# Interconnect_board_v1p4.net
KiCad netlist of a schematic drawn in EAGLE
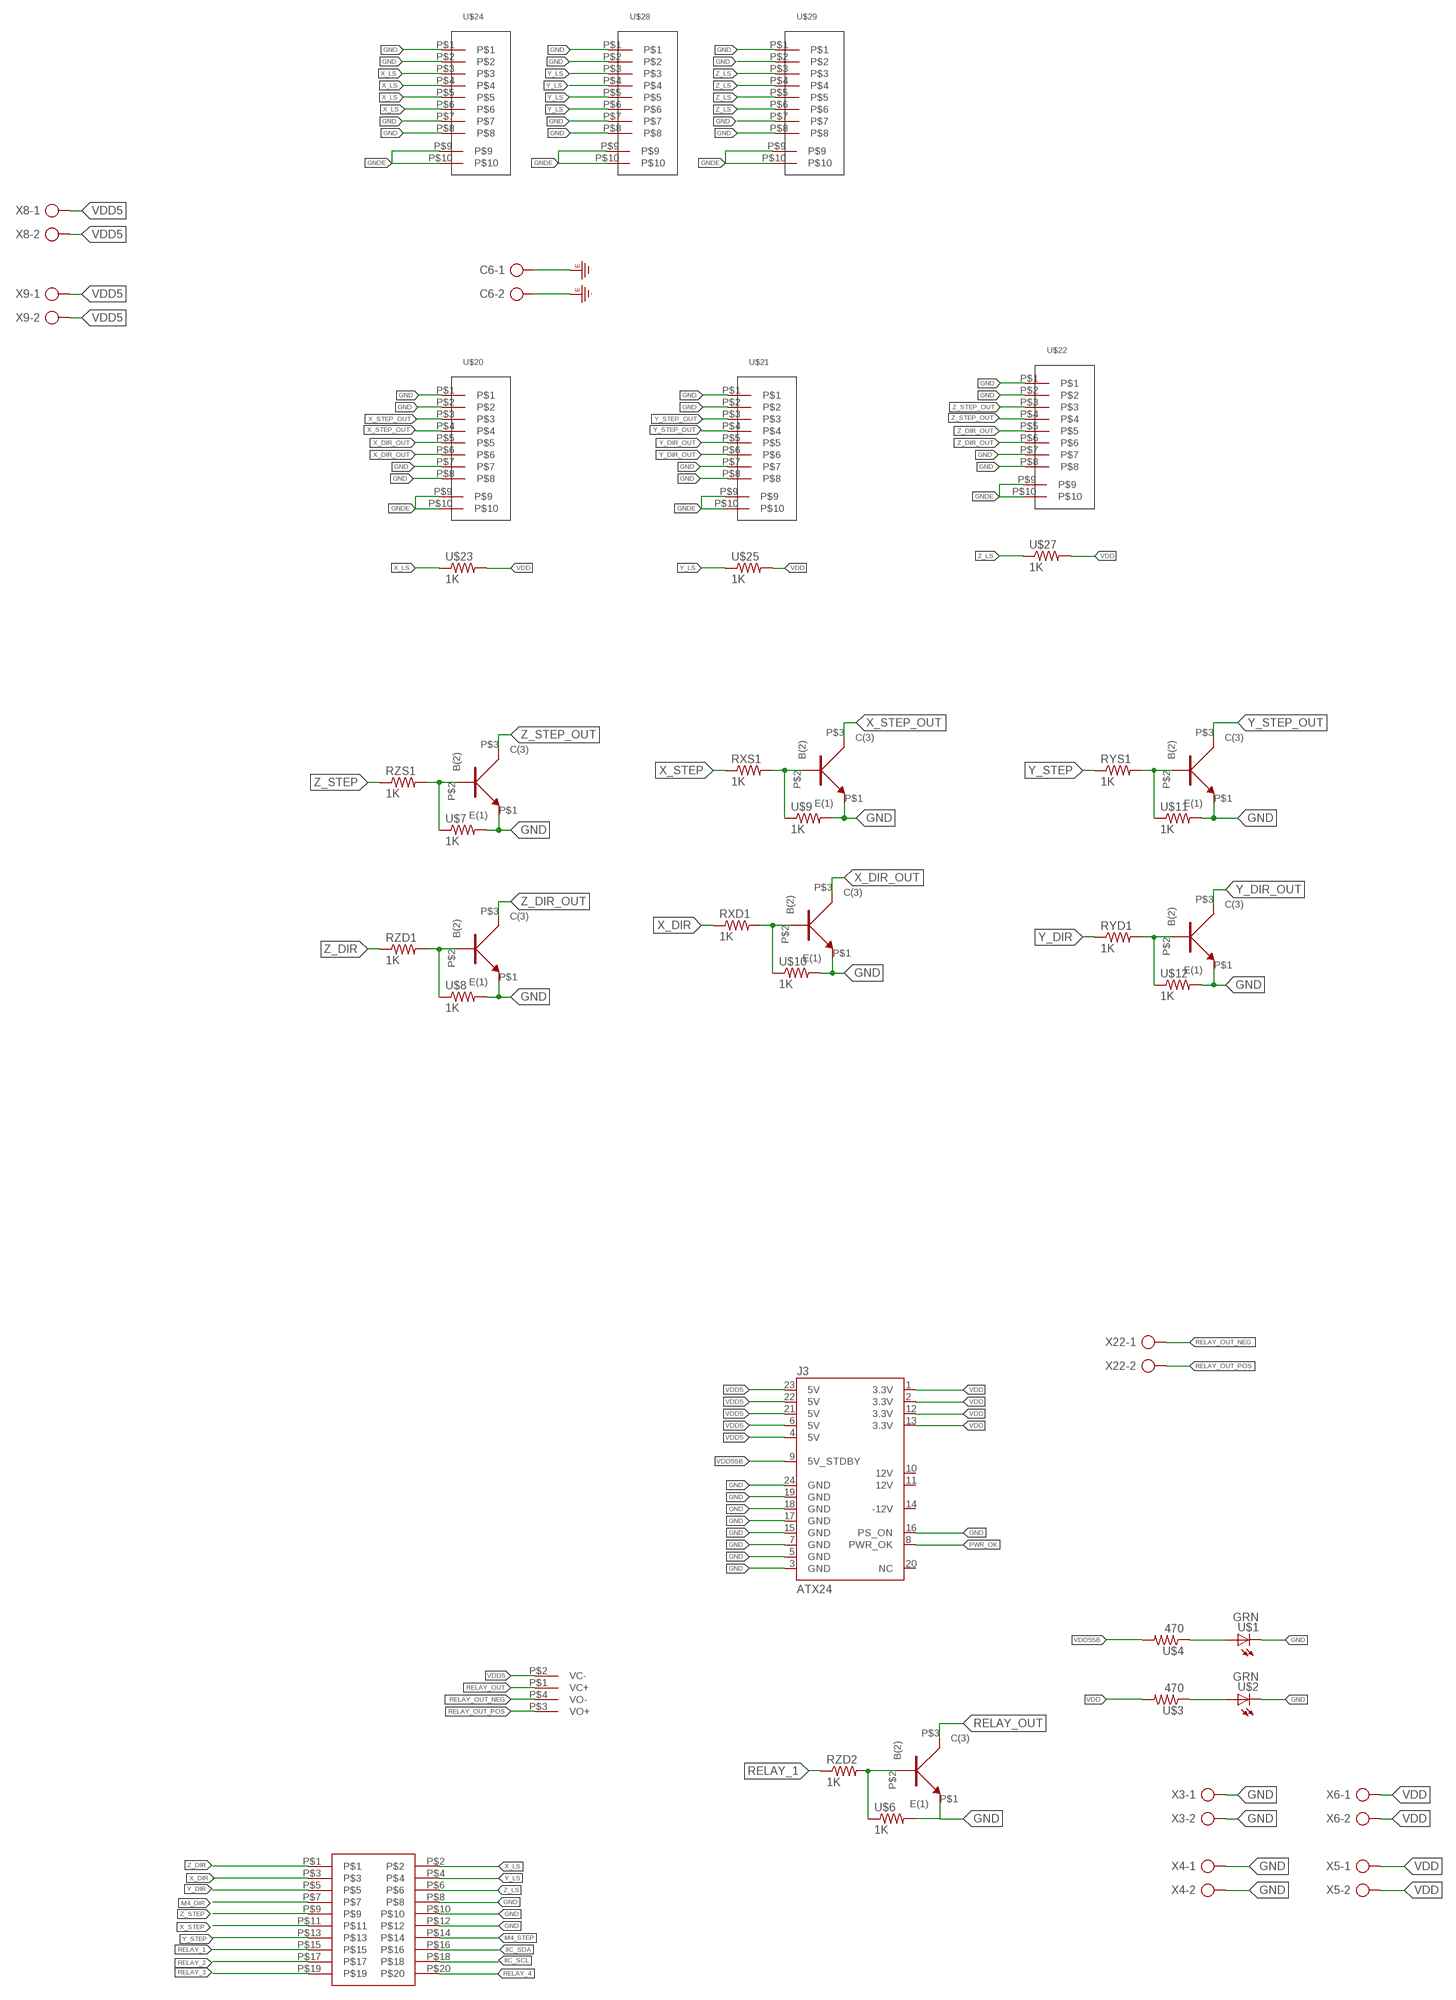
[diagram p0: schematic, sheet 1]

(export (version "E")
  (design (tool "Eeschema 10.0.6"))
  (components
    (comp (ref "C6")
      (value "AK300/2")
      (footprint "eagle-import:AK300_2")
      (libsource (lib "eagle-import") (part "AK300/2"))
    )
    (comp (ref "J3")
      (value "ATX24")
      (footprint "eagle-import:ATX24_STRAIGHT")
      (libsource (lib "eagle-import") (part "ATX24"))
    )
    (comp (ref "RXD1")
      (value "R_0805_1K")
      (footprint "eagle-import:R_0805_1K")
      (libsource (lib "eagle-import") (part "R_0805_1K"))
    )
    (comp (ref "RXS1")
      (value "R_0805_1K")
      (footprint "eagle-import:R_0805_1K")
      (libsource (lib "eagle-import") (part "R_0805_1K"))
    )
    (comp (ref "RYD1")
      (value "R_0805_1K")
      (footprint "eagle-import:R_0805_1K")
      (libsource (lib "eagle-import") (part "R_0805_1K"))
    )
    (comp (ref "RYS1")
      (value "R_0805_1K")
      (footprint "eagle-import:R_0805_1K")
      (libsource (lib "eagle-import") (part "R_0805_1K"))
    )
    (comp (ref "RZD1")
      (value "R_0805_1K")
      (footprint "eagle-import:R_0805_1K")
      (libsource (lib "eagle-import") (part "R_0805_1K"))
    )
    (comp (ref "RZD2")
      (value "R_0805_1K")
      (footprint "eagle-import:R_0805_1K")
      (libsource (lib "eagle-import") (part "R_0805_1K"))
    )
    (comp (ref "RZS1")
      (value "R_0805_1K")
      (footprint "eagle-import:R_0805_1K")
      (libsource (lib "eagle-import") (part "R_0805_1K"))
    )
    (comp (ref "U$1")
      (value "LED_0805_GREEN")
      (footprint "eagle-import:LED_0805_GREEN")
      (libsource (lib "eagle-import") (part "LED_0805_GREEN"))
    )
    (comp (ref "U$2")
      (value "LED_0805_GREEN")
      (footprint "eagle-import:LED_0805_GREEN")
      (libsource (lib "eagle-import") (part "LED_0805_GREEN"))
    )
    (comp (ref "U$3")
      (value "R_0805_470")
      (footprint "eagle-import:R_0805_470")
      (libsource (lib "eagle-import") (part "R_0805_470"))
    )
    (comp (ref "U$4")
      (value "R_0805_470")
      (footprint "eagle-import:R_0805_470")
      (libsource (lib "eagle-import") (part "R_0805_470"))
    )
    (comp (ref "U$5")
      (value "RELAY_KYOTO_KF0604D")
      (footprint "eagle-import:RELAY_KYOTO_KF0604D")
      (libsource (lib "eagle-import") (part "RELAY_KYOTO_KF0604D"))
    )
    (comp (ref "U$6")
      (value "R_0805_1K")
      (footprint "eagle-import:R_0805_1K")
      (libsource (lib "eagle-import") (part "R_0805_1K"))
    )
    (comp (ref "U$7")
      (value "R_0805_1K")
      (footprint "eagle-import:R_0805_1K")
      (libsource (lib "eagle-import") (part "R_0805_1K"))
    )
    (comp (ref "U$8")
      (value "R_0805_1K")
      (footprint "eagle-import:R_0805_1K")
      (libsource (lib "eagle-import") (part "R_0805_1K"))
    )
    (comp (ref "U$9")
      (value "R_0805_1K")
      (footprint "eagle-import:R_0805_1K")
      (libsource (lib "eagle-import") (part "R_0805_1K"))
    )
    (comp (ref "U$10")
      (value "R_0805_1K")
      (footprint "eagle-import:R_0805_1K")
      (libsource (lib "eagle-import") (part "R_0805_1K"))
    )
    (comp (ref "U$11")
      (value "R_0805_1K")
      (footprint "eagle-import:R_0805_1K")
      (libsource (lib "eagle-import") (part "R_0805_1K"))
    )
    (comp (ref "U$12")
      (value "R_0805_1K")
      (footprint "eagle-import:R_0805_1K")
      (libsource (lib "eagle-import") (part "R_0805_1K"))
    )
    (comp (ref "U$13")
      (value "TRANS_NPN")
      (footprint "eagle-import:TO_92_STRAIGHT")
      (libsource (lib "eagle-import") (part "TRANS_NPN"))
    )
    (comp (ref "U$14")
      (value "TRANS_NPN")
      (footprint "eagle-import:TO_92_STRAIGHT")
      (libsource (lib "eagle-import") (part "TRANS_NPN"))
    )
    (comp (ref "U$15")
      (value "TRANS_NPN")
      (footprint "eagle-import:TO_92_STRAIGHT")
      (libsource (lib "eagle-import") (part "TRANS_NPN"))
    )
    (comp (ref "U$16")
      (value "TRANS_NPN")
      (footprint "eagle-import:TO_92_STRAIGHT")
      (libsource (lib "eagle-import") (part "TRANS_NPN"))
    )
    (comp (ref "U$17")
      (value "TRANS_NPN")
      (footprint "eagle-import:TO_92_STRAIGHT")
      (libsource (lib "eagle-import") (part "TRANS_NPN"))
    )
    (comp (ref "U$18")
      (value "TRANS_NPN")
      (footprint "eagle-import:TO_92_STRAIGHT")
      (libsource (lib "eagle-import") (part "TRANS_NPN"))
    )
    (comp (ref "U$19")
      (value "TRANS_NPN")
      (footprint "eagle-import:TO_92_STRAIGHT")
      (libsource (lib "eagle-import") (part "TRANS_NPN"))
    )
    (comp (ref "U$20")
      (value "RJ45_SMTRJ")
      (footprint "eagle-import:RJ45_SMT")
      (libsource (lib "eagle-import") (part "RJ45_SMTRJ"))
    )
    (comp (ref "U$21")
      (value "RJ45_SMTRJ")
      (footprint "eagle-import:RJ45_SMT")
      (libsource (lib "eagle-import") (part "RJ45_SMTRJ"))
    )
    (comp (ref "U$22")
      (value "RJ45_SMTRJ")
      (footprint "eagle-import:RJ45_SMT")
      (libsource (lib "eagle-import") (part "RJ45_SMTRJ"))
    )
    (comp (ref "U$23")
      (value "R_0805_1K")
      (footprint "eagle-import:R_0805_1K")
      (libsource (lib "eagle-import") (part "R_0805_1K"))
    )
    (comp (ref "U$24")
      (value "RJ45_SMTRJ")
      (footprint "eagle-import:RJ45_SMT")
      (libsource (lib "eagle-import") (part "RJ45_SMTRJ"))
    )
    (comp (ref "U$25")
      (value "R_0805_1K")
      (footprint "eagle-import:R_0805_1K")
      (libsource (lib "eagle-import") (part "R_0805_1K"))
    )
    (comp (ref "U$26")
      (value "2_X_10_HEADER_GENERIC")
      (footprint "eagle-import:2_X_10_.1_INCH")
      (libsource (lib "eagle-import") (part "2_X_10_HEADER_GENERIC"))
    )
    (comp (ref "U$27")
      (value "R_0805_1K")
      (footprint "eagle-import:R_0805_1K")
      (libsource (lib "eagle-import") (part "R_0805_1K"))
    )
    (comp (ref "U$28")
      (value "RJ45_SMTRJ")
      (footprint "eagle-import:RJ45_SMT")
      (libsource (lib "eagle-import") (part "RJ45_SMTRJ"))
    )
    (comp (ref "U$29")
      (value "RJ45_SMTRJ")
      (footprint "eagle-import:RJ45_SMT")
      (libsource (lib "eagle-import") (part "RJ45_SMTRJ"))
    )
    (comp (ref "X3")
      (value "AK300/2")
      (footprint "eagle-import:AK300_2")
      (libsource (lib "eagle-import") (part "AK300/2"))
    )
    (comp (ref "X4")
      (value "AK300/2")
      (footprint "eagle-import:AK300_2")
      (libsource (lib "eagle-import") (part "AK300/2"))
    )
    (comp (ref "X5")
      (value "AK300/2")
      (footprint "eagle-import:AK300_2")
      (libsource (lib "eagle-import") (part "AK300/2"))
    )
    (comp (ref "X6")
      (value "AK300/2")
      (footprint "eagle-import:AK300_2")
      (libsource (lib "eagle-import") (part "AK300/2"))
    )
    (comp (ref "X8")
      (value "AK300/2")
      (footprint "eagle-import:AK300_2")
      (libsource (lib "eagle-import") (part "AK300/2"))
    )
    (comp (ref "X9")
      (value "AK300/2")
      (footprint "eagle-import:AK300_2")
      (libsource (lib "eagle-import") (part "AK300/2"))
    )
    (comp (ref "X22")
      (value "AK300/2")
      (footprint "eagle-import:AK300_2")
      (libsource (lib "eagle-import") (part "AK300/2"))
    )
  )
  (nets
    (net (code "1") (name "GND") (class "Default")
      (node (ref "J3") (pin "15") (pinfunction "GND_15") (pintype "bidirectional"))
      (node (ref "J3") (pin "16") (pinfunction "PS_ON_16") (pintype "bidirectional"))
      (node (ref "J3") (pin "17") (pinfunction "GND_17") (pintype "bidirectional"))
      (node (ref "J3") (pin "18") (pinfunction "GND_18") (pintype "bidirectional"))
      (node (ref "J3") (pin "19") (pinfunction "GND_19") (pintype "bidirectional"))
      (node (ref "J3") (pin "24") (pinfunction "GND_24") (pintype "bidirectional"))
      (node (ref "J3") (pin "3") (pinfunction "GND_3") (pintype "bidirectional"))
      (node (ref "J3") (pin "5") (pinfunction "GND_5") (pintype "bidirectional"))
      (node (ref "J3") (pin "7") (pinfunction "GND_7") (pintype "bidirectional"))
      (node (ref "U$1") (pin "C") (pinfunction "C_C") (pintype "passive"))
      (node (ref "U$10") (pin "2") (pinfunction "2_2") (pintype "passive"))
      (node (ref "U$11") (pin "2") (pinfunction "2_2") (pintype "passive"))
      (node (ref "U$12") (pin "2") (pinfunction "2_2") (pintype "passive"))
      (node (ref "U$13") (pin "P$1") (pinfunction "E(1)_P$1") (pintype "output"))
      (node (ref "U$14") (pin "P$1") (pinfunction "E(1)_P$1") (pintype "output"))
      (node (ref "U$15") (pin "P$1") (pinfunction "E(1)_P$1") (pintype "output"))
      (node (ref "U$16") (pin "P$1") (pinfunction "E(1)_P$1") (pintype "output"))
      (node (ref "U$17") (pin "P$1") (pinfunction "E(1)_P$1") (pintype "output"))
      (node (ref "U$18") (pin "P$1") (pinfunction "E(1)_P$1") (pintype "output"))
      (node (ref "U$19") (pin "P$1") (pinfunction "E(1)_P$1") (pintype "output"))
      (node (ref "U$2") (pin "C") (pinfunction "C_C") (pintype "passive"))
      (node (ref "U$20") (pin "P$1") (pinfunction "P$1_P$1") (pintype "bidirectional"))
      (node (ref "U$20") (pin "P$2") (pinfunction "P$2_P$2") (pintype "bidirectional"))
      (node (ref "U$20") (pin "P$7") (pinfunction "P$7_P$7") (pintype "bidirectional"))
      (node (ref "U$20") (pin "P$8") (pinfunction "P$8_P$8") (pintype "bidirectional"))
      (node (ref "U$21") (pin "P$1") (pinfunction "P$1_P$1") (pintype "bidirectional"))
      (node (ref "U$21") (pin "P$2") (pinfunction "P$2_P$2") (pintype "bidirectional"))
      (node (ref "U$21") (pin "P$7") (pinfunction "P$7_P$7") (pintype "bidirectional"))
      (node (ref "U$21") (pin "P$8") (pinfunction "P$8_P$8") (pintype "bidirectional"))
      (node (ref "U$22") (pin "P$1") (pinfunction "P$1_P$1") (pintype "bidirectional"))
      (node (ref "U$22") (pin "P$2") (pinfunction "P$2_P$2") (pintype "bidirectional"))
      (node (ref "U$22") (pin "P$7") (pinfunction "P$7_P$7") (pintype "bidirectional"))
      (node (ref "U$22") (pin "P$8") (pinfunction "P$8_P$8") (pintype "bidirectional"))
      (node (ref "U$24") (pin "P$1") (pinfunction "P$1_P$1") (pintype "bidirectional"))
      (node (ref "U$24") (pin "P$2") (pinfunction "P$2_P$2") (pintype "bidirectional"))
      (node (ref "U$24") (pin "P$7") (pinfunction "P$7_P$7") (pintype "bidirectional"))
      (node (ref "U$24") (pin "P$8") (pinfunction "P$8_P$8") (pintype "bidirectional"))
      (node (ref "U$26") (pin "P$10") (pinfunction "P$10_P$10") (pintype "bidirectional"))
      (node (ref "U$26") (pin "P$12") (pinfunction "P$12_P$12") (pintype "bidirectional"))
      (node (ref "U$26") (pin "P$8") (pinfunction "P$8_P$8") (pintype "bidirectional"))
      (node (ref "U$28") (pin "P$1") (pinfunction "P$1_P$1") (pintype "bidirectional"))
      (node (ref "U$28") (pin "P$2") (pinfunction "P$2_P$2") (pintype "bidirectional"))
      (node (ref "U$28") (pin "P$7") (pinfunction "P$7_P$7") (pintype "bidirectional"))
      (node (ref "U$28") (pin "P$8") (pinfunction "P$8_P$8") (pintype "bidirectional"))
      (node (ref "U$29") (pin "P$1") (pinfunction "P$1_P$1") (pintype "bidirectional"))
      (node (ref "U$29") (pin "P$2") (pinfunction "P$2_P$2") (pintype "bidirectional"))
      (node (ref "U$29") (pin "P$7") (pinfunction "P$7_P$7") (pintype "bidirectional"))
      (node (ref "U$29") (pin "P$8") (pinfunction "P$8_P$8") (pintype "bidirectional"))
      (node (ref "U$6") (pin "2") (pinfunction "2_2") (pintype "passive"))
      (node (ref "U$7") (pin "2") (pinfunction "2_2") (pintype "passive"))
      (node (ref "U$8") (pin "2") (pinfunction "2_2") (pintype "passive"))
      (node (ref "U$9") (pin "2") (pinfunction "2_2") (pintype "passive"))
      (node (ref "X3") (pin "1") (pinfunction "KL_1") (pintype "passive"))
      (node (ref "X3") (pin "2") (pinfunction "KL_2") (pintype "passive"))
      (node (ref "X4") (pin "1") (pinfunction "KL_1") (pintype "passive"))
      (node (ref "X4") (pin "2") (pinfunction "KL_2") (pintype "passive"))
    )
    (net (code "2") (name "GNDE") (class "Default")
      (node (ref "C6") (pin "1") (pinfunction "KL_1") (pintype "passive"))
      (node (ref "C6") (pin "2") (pinfunction "KL_2") (pintype "passive"))
      (node (ref "U$20") (pin "P$10") (pinfunction "P$10_P$10") (pintype "bidirectional"))
      (node (ref "U$20") (pin "P$9") (pinfunction "P$9_P$9") (pintype "bidirectional"))
      (node (ref "U$21") (pin "P$10") (pinfunction "P$10_P$10") (pintype "bidirectional"))
      (node (ref "U$21") (pin "P$9") (pinfunction "P$9_P$9") (pintype "bidirectional"))
      (node (ref "U$22") (pin "P$10") (pinfunction "P$10_P$10") (pintype "bidirectional"))
      (node (ref "U$22") (pin "P$9") (pinfunction "P$9_P$9") (pintype "bidirectional"))
      (node (ref "U$24") (pin "P$10") (pinfunction "P$10_P$10") (pintype "bidirectional"))
      (node (ref "U$24") (pin "P$9") (pinfunction "P$9_P$9") (pintype "bidirectional"))
      (node (ref "U$28") (pin "P$10") (pinfunction "P$10_P$10") (pintype "bidirectional"))
      (node (ref "U$28") (pin "P$9") (pinfunction "P$9_P$9") (pintype "bidirectional"))
      (node (ref "U$29") (pin "P$10") (pinfunction "P$10_P$10") (pintype "bidirectional"))
      (node (ref "U$29") (pin "P$9") (pinfunction "P$9_P$9") (pintype "bidirectional"))
    )
    (net (code "3") (name "IIC_SCL") (class "Default")
      (node (ref "U$26") (pin "P$18") (pinfunction "P$18_P$18") (pintype "bidirectional"))
    )
    (net (code "4") (name "IIC_SDA") (class "Default")
      (node (ref "U$26") (pin "P$16") (pinfunction "P$16_P$16") (pintype "bidirectional"))
    )
    (net (code "5") (name "M4_DIR") (class "Default")
      (node (ref "U$26") (pin "P$7") (pinfunction "P$7_P$7") (pintype "bidirectional"))
    )
    (net (code "6") (name "M4_STEP") (class "Default")
      (node (ref "U$26") (pin "P$14") (pinfunction "P$14_P$14") (pintype "bidirectional"))
    )
    (net (code "7") (name "Net-(U$1-PadA)") (class "Default")
      (node (ref "U$1") (pin "A") (pinfunction "A_A") (pintype "passive"))
      (node (ref "U$4") (pin "1") (pinfunction "1_1") (pintype "passive"))
    )
    (net (code "8") (name "Net-(U$2-PadA)") (class "Default")
      (node (ref "U$2") (pin "A") (pinfunction "A_A") (pintype "passive"))
      (node (ref "U$3") (pin "1") (pinfunction "1_1") (pintype "passive"))
    )
    (net (code "9") (name "Net-(U$13-B(2))") (class "Default")
      (node (ref "RZS1") (pin "2") (pinfunction "2_2") (pintype "passive"))
      (node (ref "U$13") (pin "P$2") (pinfunction "B(2)_P$2") (pintype "input"))
      (node (ref "U$7") (pin "1") (pinfunction "1_1") (pintype "passive"))
    )
    (net (code "10") (name "Net-(U$14-B(2))") (class "Default")
      (node (ref "RZD1") (pin "2") (pinfunction "2_2") (pintype "passive"))
      (node (ref "U$14") (pin "P$2") (pinfunction "B(2)_P$2") (pintype "input"))
      (node (ref "U$8") (pin "1") (pinfunction "1_1") (pintype "passive"))
    )
    (net (code "11") (name "Net-(U$15-B(2))") (class "Default")
      (node (ref "RXS1") (pin "2") (pinfunction "2_2") (pintype "passive"))
      (node (ref "U$15") (pin "P$2") (pinfunction "B(2)_P$2") (pintype "input"))
      (node (ref "U$9") (pin "1") (pinfunction "1_1") (pintype "passive"))
    )
    (net (code "12") (name "Net-(U$16-B(2))") (class "Default")
      (node (ref "RXD1") (pin "2") (pinfunction "2_2") (pintype "passive"))
      (node (ref "U$10") (pin "1") (pinfunction "1_1") (pintype "passive"))
      (node (ref "U$16") (pin "P$2") (pinfunction "B(2)_P$2") (pintype "input"))
    )
    (net (code "13") (name "Net-(U$17-B(2))") (class "Default")
      (node (ref "RYD1") (pin "2") (pinfunction "2_2") (pintype "passive"))
      (node (ref "U$12") (pin "1") (pinfunction "1_1") (pintype "passive"))
      (node (ref "U$17") (pin "P$2") (pinfunction "B(2)_P$2") (pintype "input"))
    )
    (net (code "14") (name "Net-(U$18-B(2))") (class "Default")
      (node (ref "RYS1") (pin "2") (pinfunction "2_2") (pintype "passive"))
      (node (ref "U$11") (pin "1") (pinfunction "1_1") (pintype "passive"))
      (node (ref "U$18") (pin "P$2") (pinfunction "B(2)_P$2") (pintype "input"))
    )
    (net (code "15") (name "Net-(U$19-B(2))") (class "Default")
      (node (ref "RZD2") (pin "2") (pinfunction "2_2") (pintype "passive"))
      (node (ref "U$19") (pin "P$2") (pinfunction "B(2)_P$2") (pintype "input"))
      (node (ref "U$6") (pin "1") (pinfunction "1_1") (pintype "passive"))
    )
    (net (code "16") (name "PWR_OK") (class "Default")
      (node (ref "J3") (pin "8") (pinfunction "PWR_OK_8") (pintype "bidirectional"))
    )
    (net (code "17") (name "RELAY_1") (class "Default")
      (node (ref "RZD2") (pin "1") (pinfunction "1_1") (pintype "passive"))
      (node (ref "U$26") (pin "P$15") (pinfunction "P$15_P$15") (pintype "bidirectional"))
    )
    (net (code "18") (name "RELAY_2") (class "Default")
      (node (ref "U$26") (pin "P$17") (pinfunction "P$17_P$17") (pintype "bidirectional"))
    )
    (net (code "19") (name "RELAY_3") (class "Default")
      (node (ref "U$26") (pin "P$19") (pinfunction "P$19_P$19") (pintype "bidirectional"))
    )
    (net (code "20") (name "RELAY_4") (class "Default")
      (node (ref "U$26") (pin "P$20") (pinfunction "P$20_P$20") (pintype "bidirectional"))
    )
    (net (code "21") (name "RELAY_OUT") (class "Default")
      (node (ref "U$19") (pin "P$3") (pinfunction "C(3)_P$3") (pintype "input"))
      (node (ref "U$5") (pin "P$1") (pinfunction "VC+_P$1") (pintype "bidirectional"))
    )
    (net (code "22") (name "RELAY_OUT_NEG") (class "Default")
      (node (ref "U$5") (pin "P$4") (pinfunction "VO-_P$4") (pintype "bidirectional"))
      (node (ref "X22") (pin "1") (pinfunction "KL_1") (pintype "passive"))
    )
    (net (code "23") (name "RELAY_OUT_POS") (class "Default")
      (node (ref "U$5") (pin "P$3") (pinfunction "VO+_P$3") (pintype "bidirectional"))
      (node (ref "X22") (pin "2") (pinfunction "KL_2") (pintype "passive"))
    )
    (net (code "24") (name "VDD") (class "Default")
      (node (ref "J3") (pin "1") (pinfunction "3.3V_1") (pintype "bidirectional"))
      (node (ref "J3") (pin "12") (pinfunction "3.3V_12") (pintype "bidirectional"))
      (node (ref "J3") (pin "13") (pinfunction "3.3V_13") (pintype "bidirectional"))
      (node (ref "J3") (pin "2") (pinfunction "3.3V_2") (pintype "bidirectional"))
      (node (ref "U$23") (pin "2") (pinfunction "2_2") (pintype "passive"))
      (node (ref "U$25") (pin "2") (pinfunction "2_2") (pintype "passive"))
      (node (ref "U$27") (pin "2") (pinfunction "2_2") (pintype "passive"))
      (node (ref "U$3") (pin "2") (pinfunction "2_2") (pintype "passive"))
      (node (ref "X5") (pin "1") (pinfunction "KL_1") (pintype "passive"))
      (node (ref "X5") (pin "2") (pinfunction "KL_2") (pintype "passive"))
      (node (ref "X6") (pin "1") (pinfunction "KL_1") (pintype "passive"))
      (node (ref "X6") (pin "2") (pinfunction "KL_2") (pintype "passive"))
    )
    (net (code "25") (name "VDD5") (class "Default")
      (node (ref "J3") (pin "21") (pinfunction "5V_21") (pintype "bidirectional"))
      (node (ref "J3") (pin "22") (pinfunction "5V_22") (pintype "bidirectional"))
      (node (ref "J3") (pin "23") (pinfunction "5V_23") (pintype "bidirectional"))
      (node (ref "J3") (pin "4") (pinfunction "5V_4") (pintype "bidirectional"))
      (node (ref "J3") (pin "6") (pinfunction "5V_6") (pintype "bidirectional"))
      (node (ref "U$5") (pin "P$2") (pinfunction "VC-_P$2") (pintype "bidirectional"))
      (node (ref "X8") (pin "1") (pinfunction "KL_1") (pintype "passive"))
      (node (ref "X8") (pin "2") (pinfunction "KL_2") (pintype "passive"))
      (node (ref "X9") (pin "1") (pinfunction "KL_1") (pintype "passive"))
      (node (ref "X9") (pin "2") (pinfunction "KL_2") (pintype "passive"))
    )
    (net (code "26") (name "VDD5SB") (class "Default")
      (node (ref "J3") (pin "9") (pinfunction "5V_STDBY_9") (pintype "bidirectional"))
      (node (ref "U$4") (pin "2") (pinfunction "2_2") (pintype "passive"))
    )
    (net (code "27") (name "X_DIR") (class "Default")
      (node (ref "RXD1") (pin "1") (pinfunction "1_1") (pintype "passive"))
      (node (ref "U$26") (pin "P$3") (pinfunction "P$3_P$3") (pintype "bidirectional"))
    )
    (net (code "28") (name "X_DIR_OUT") (class "Default")
      (node (ref "U$16") (pin "P$3") (pinfunction "C(3)_P$3") (pintype "input"))
      (node (ref "U$20") (pin "P$5") (pinfunction "P$5_P$5") (pintype "bidirectional"))
      (node (ref "U$20") (pin "P$6") (pinfunction "P$6_P$6") (pintype "bidirectional"))
    )
    (net (code "29") (name "X_LS") (class "Default")
      (node (ref "U$23") (pin "1") (pinfunction "1_1") (pintype "passive"))
      (node (ref "U$24") (pin "P$3") (pinfunction "P$3_P$3") (pintype "bidirectional"))
      (node (ref "U$24") (pin "P$4") (pinfunction "P$4_P$4") (pintype "bidirectional"))
      (node (ref "U$24") (pin "P$5") (pinfunction "P$5_P$5") (pintype "bidirectional"))
      (node (ref "U$24") (pin "P$6") (pinfunction "P$6_P$6") (pintype "bidirectional"))
      (node (ref "U$26") (pin "P$2") (pinfunction "P$2_P$2") (pintype "bidirectional"))
    )
    (net (code "30") (name "X_STEP") (class "Default")
      (node (ref "RXS1") (pin "1") (pinfunction "1_1") (pintype "passive"))
      (node (ref "U$26") (pin "P$11") (pinfunction "P$11_P$11") (pintype "bidirectional"))
    )
    (net (code "31") (name "X_STEP_OUT") (class "Default")
      (node (ref "U$15") (pin "P$3") (pinfunction "C(3)_P$3") (pintype "input"))
      (node (ref "U$20") (pin "P$3") (pinfunction "P$3_P$3") (pintype "bidirectional"))
      (node (ref "U$20") (pin "P$4") (pinfunction "P$4_P$4") (pintype "bidirectional"))
    )
    (net (code "32") (name "Y_DIR") (class "Default")
      (node (ref "RYD1") (pin "1") (pinfunction "1_1") (pintype "passive"))
      (node (ref "U$26") (pin "P$5") (pinfunction "P$5_P$5") (pintype "bidirectional"))
    )
    (net (code "33") (name "Y_DIR_OUT") (class "Default")
      (node (ref "U$17") (pin "P$3") (pinfunction "C(3)_P$3") (pintype "input"))
      (node (ref "U$21") (pin "P$5") (pinfunction "P$5_P$5") (pintype "bidirectional"))
      (node (ref "U$21") (pin "P$6") (pinfunction "P$6_P$6") (pintype "bidirectional"))
    )
    (net (code "34") (name "Y_LS") (class "Default")
      (node (ref "U$25") (pin "1") (pinfunction "1_1") (pintype "passive"))
      (node (ref "U$26") (pin "P$4") (pinfunction "P$4_P$4") (pintype "bidirectional"))
      (node (ref "U$28") (pin "P$3") (pinfunction "P$3_P$3") (pintype "bidirectional"))
      (node (ref "U$28") (pin "P$4") (pinfunction "P$4_P$4") (pintype "bidirectional"))
      (node (ref "U$28") (pin "P$5") (pinfunction "P$5_P$5") (pintype "bidirectional"))
      (node (ref "U$28") (pin "P$6") (pinfunction "P$6_P$6") (pintype "bidirectional"))
    )
    (net (code "35") (name "Y_STEP") (class "Default")
      (node (ref "RYS1") (pin "1") (pinfunction "1_1") (pintype "passive"))
      (node (ref "U$26") (pin "P$13") (pinfunction "P$13_P$13") (pintype "bidirectional"))
    )
    (net (code "36") (name "Y_STEP_OUT") (class "Default")
      (node (ref "U$18") (pin "P$3") (pinfunction "C(3)_P$3") (pintype "input"))
      (node (ref "U$21") (pin "P$3") (pinfunction "P$3_P$3") (pintype "bidirectional"))
      (node (ref "U$21") (pin "P$4") (pinfunction "P$4_P$4") (pintype "bidirectional"))
    )
    (net (code "37") (name "Z_DIR") (class "Default")
      (node (ref "RZD1") (pin "1") (pinfunction "1_1") (pintype "passive"))
      (node (ref "U$26") (pin "P$1") (pinfunction "P$1_P$1") (pintype "bidirectional"))
    )
    (net (code "38") (name "Z_DIR_OUT") (class "Default")
      (node (ref "U$14") (pin "P$3") (pinfunction "C(3)_P$3") (pintype "input"))
      (node (ref "U$22") (pin "P$5") (pinfunction "P$5_P$5") (pintype "bidirectional"))
      (node (ref "U$22") (pin "P$6") (pinfunction "P$6_P$6") (pintype "bidirectional"))
    )
    (net (code "39") (name "Z_LS") (class "Default")
      (node (ref "U$26") (pin "P$6") (pinfunction "P$6_P$6") (pintype "bidirectional"))
      (node (ref "U$27") (pin "1") (pinfunction "1_1") (pintype "passive"))
      (node (ref "U$29") (pin "P$3") (pinfunction "P$3_P$3") (pintype "bidirectional"))
      (node (ref "U$29") (pin "P$4") (pinfunction "P$4_P$4") (pintype "bidirectional"))
      (node (ref "U$29") (pin "P$5") (pinfunction "P$5_P$5") (pintype "bidirectional"))
      (node (ref "U$29") (pin "P$6") (pinfunction "P$6_P$6") (pintype "bidirectional"))
    )
    (net (code "40") (name "Z_STEP") (class "Default")
      (node (ref "RZS1") (pin "1") (pinfunction "1_1") (pintype "passive"))
      (node (ref "U$26") (pin "P$9") (pinfunction "P$9_P$9") (pintype "bidirectional"))
    )
    (net (code "41") (name "Z_STEP_OUT") (class "Default")
      (node (ref "U$13") (pin "P$3") (pinfunction "C(3)_P$3") (pintype "input"))
      (node (ref "U$22") (pin "P$3") (pinfunction "P$3_P$3") (pintype "bidirectional"))
      (node (ref "U$22") (pin "P$4") (pinfunction "P$4_P$4") (pintype "bidirectional"))
    )
    (net (code "42") (name "unconnected-(J3--12V-Pad14)") (class "Default")
      (node (ref "J3") (pin "14") (pinfunction "-12V_14") (pintype "bidirectional"))
    )
    (net (code "43") (name "unconnected-(J3-12V-Pad10)") (class "Default")
      (node (ref "J3") (pin "10") (pinfunction "12V_10") (pintype "bidirectional"))
    )
    (net (code "44") (name "unconnected-(J3-12V-Pad11)") (class "Default")
      (node (ref "J3") (pin "11") (pinfunction "12V_11") (pintype "bidirectional"))
    )
    (net (code "45") (name "unconnected-(J3-NC-Pad20)") (class "Default")
      (node (ref "J3") (pin "20") (pinfunction "NC_20") (pintype "bidirectional"))
    )
  )
)
